# TEMP.net
KiCad netlist of a schematic drawn in Altium Designer
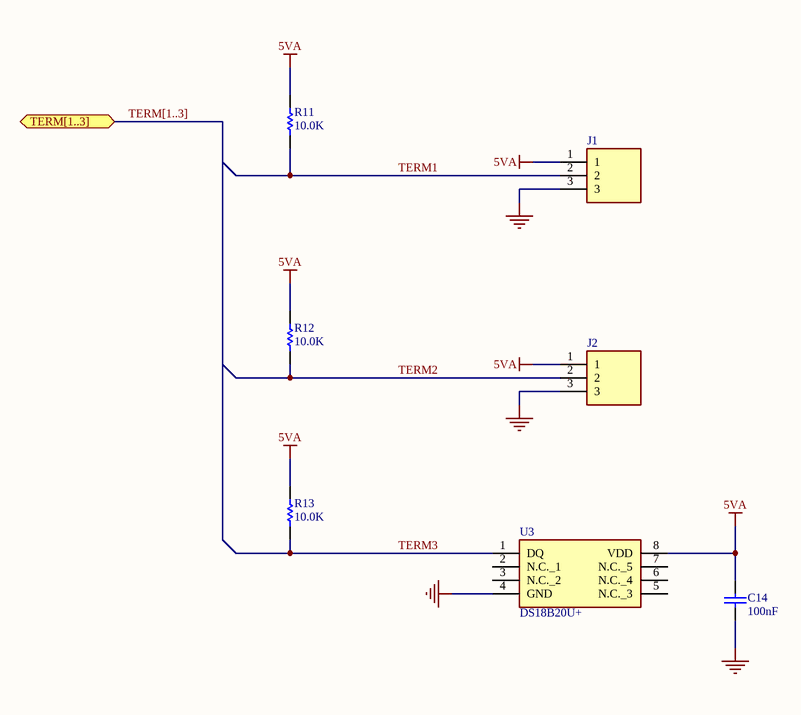
[diagram p0: TEMP.SchDoc]

(export (version "E")
  (design (tool "Eeschema 10.0.6"))
  (components
    (comp (ref "C14")
      (value "100nF")
      (footprint "CAP_0603_H090 (_IPC_MD)")
      (description "CAP CER 100NF 50V X7R 0603")
      (fields (field (name "PART NUMBER") "CL10B104KB8NNNC") (field (name "Comment") "100nF 0603"))
      (libsource (lib "MUAB_Altium_Lib") (part "CAP"))
    )
    (comp (ref "J1")
      (value "B3B-PH-K-S_LF__SN_")
      (footprint "OpenBrewie:SHDR3W50P0X200_1X3_790X450X600P")
      (description "Connector")
      (fields (field (name "MANUFACTURER_PART_NUMBER") "B3B-PH-K-S(LF)(SN)"))
      (libsource (lib "OpenBrewie") (part "B3B-PH-K-S_LF__SN_"))
    )
    (comp (ref "J2")
      (value "B3B-PH-K-S_LF__SN_")
      (footprint "OpenBrewie:SHDR3W50P0X200_1X3_790X450X600P")
      (description "Connector")
      (fields (field (name "MANUFACTURER_PART_NUMBER") "B3B-PH-K-S(LF)(SN)"))
      (libsource (lib "OpenBrewie") (part "B3B-PH-K-S_LF__SN_"))
    )
    (comp (ref "R11")
      (value "10.0K")
      (footprint "RES_0603_H050 (_IPC_MD)")
      (description "10.0K 1% 0,1W 75V 0603")
      (fields (field (name "PART NUMBER") "RES10.0K1%0603"))
      (libsource (lib "MUAB_Altium_Lib") (part "RES"))
    )
    (comp (ref "R12")
      (value "10.0K")
      (footprint "RES_0603_H050 (_IPC_MD)")
      (description "10.0K 1% 0,1W 75V 0603")
      (fields (field (name "PART NUMBER") "RES10.0K1%0603"))
      (libsource (lib "MUAB_Altium_Lib") (part "RES"))
    )
    (comp (ref "R13")
      (value "10.0K")
      (footprint "RES_0603_H050 (_IPC_MD)")
      (description "10.0K 1% 0,1W 75V 0603")
      (fields (field (name "PART NUMBER") "RES10.0K1%0603"))
      (libsource (lib "MUAB_Altium_Lib") (part "RES"))
    )
    (comp (ref "U3")
      (value "DS18B20U+")
      (footprint "OpenBrewie:SOP65P490X110-8N")
      (description "Te,perature sensor")
      (fields (field (name "MOUSER PART NUMBER") "700-DS18B20U"))
      (libsource (lib "OpenBrewie") (part "DS18B20U+"))
    )
  )
  (nets
    (net (code "1") (name "/TERM1") (class "Default")
      (node (ref "J1") (pin "2") (pinfunction "2_2") (pintype "passive"))
      (node (ref "R11") (pin "2") (pinfunction "2_2") (pintype "passive"))
    )
    (net (code "2") (name "/TERM2") (class "Default")
      (node (ref "J2") (pin "2") (pinfunction "2_2") (pintype "passive"))
      (node (ref "R12") (pin "2") (pinfunction "2_2") (pintype "passive"))
    )
    (net (code "3") (name "/TERM3") (class "Default")
      (node (ref "R13") (pin "2") (pinfunction "2_2") (pintype "passive"))
      (node (ref "U3") (pin "1") (pinfunction "DQ_1") (pintype "passive"))
    )
    (net (code "5") (name "5VA") (class "Default")
      (node (ref "C14") (pin "2") (pinfunction "2_2") (pintype "passive"))
      (node (ref "J1") (pin "1") (pinfunction "1_1") (pintype "passive"))
      (node (ref "J2") (pin "1") (pinfunction "1_1") (pintype "passive"))
      (node (ref "R11") (pin "1") (pinfunction "1_1") (pintype "passive"))
      (node (ref "R12") (pin "1") (pinfunction "1_1") (pintype "passive"))
      (node (ref "R13") (pin "1") (pinfunction "1_1") (pintype "passive"))
      (node (ref "U3") (pin "8") (pinfunction "VDD_8") (pintype "passive"))
    )
    (net (code "6") (name "GND") (class "Default")
      (node (ref "C14") (pin "1") (pinfunction "1_1") (pintype "passive"))
      (node (ref "J1") (pin "3") (pinfunction "3_3") (pintype "passive"))
      (node (ref "J2") (pin "3") (pinfunction "3_3") (pintype "passive"))
      (node (ref "U3") (pin "4") (pinfunction "GND_4") (pintype "passive"))
    )
    (net (code "7") (name "unconnected-(U3-N.C._1-Pad2)") (class "Default")
      (node (ref "U3") (pin "2") (pinfunction "N.C._1_2") (pintype "passive"))
    )
    (net (code "8") (name "unconnected-(U3-N.C._2-Pad3)") (class "Default")
      (node (ref "U3") (pin "3") (pinfunction "N.C._2_3") (pintype "passive"))
    )
    (net (code "9") (name "unconnected-(U3-N.C._3-Pad5)") (class "Default")
      (node (ref "U3") (pin "5") (pinfunction "N.C._3_5") (pintype "passive"))
    )
    (net (code "10") (name "unconnected-(U3-N.C._4-Pad6)") (class "Default")
      (node (ref "U3") (pin "6") (pinfunction "N.C._4_6") (pintype "passive"))
    )
    (net (code "11") (name "unconnected-(U3-N.C._5-Pad7)") (class "Default")
      (node (ref "U3") (pin "7") (pinfunction "N.C._5_7") (pintype "passive"))
    )
  )
)
